# Buttons.net
KiCad netlist of a schematic drawn in Altium Designer
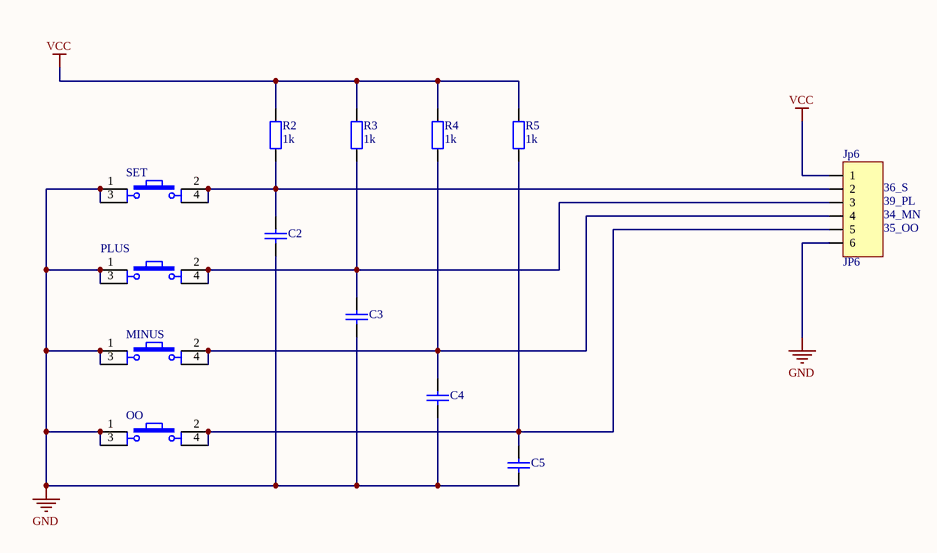
[diagram p0: Buttons.SchDoc]

(export (version "E")
  (design (tool "Eeschema 10.0.6"))
  (components
    (comp (ref "C2")
      (value "Capacitor Ceramic")
      (footprint "C0805")
      (description "Capacitor")
      (fields (field (name "PUBLISHER") "Altium Limited"))
      (libsource (lib "NBBLib 14-03-2012") (part "CapSMD"))
    )
    (comp (ref "C3")
      (value "Capacitor Ceramic")
      (footprint "C0805")
      (description "Capacitor")
      (fields (field (name "PUBLISHER") "Altium Limited"))
      (libsource (lib "NBBLib 14-03-2012") (part "CapSMD"))
    )
    (comp (ref "C4")
      (value "Capacitor Ceramic")
      (footprint "C0805")
      (description "Capacitor")
      (fields (field (name "PUBLISHER") "Altium Limited"))
      (libsource (lib "NBBLib 14-03-2012") (part "CapSMD"))
    )
    (comp (ref "C5")
      (value "Capacitor Ceramic")
      (footprint "C0805")
      (description "Capacitor")
      (fields (field (name "PUBLISHER") "Altium Limited"))
      (libsource (lib "NBBLib 14-03-2012") (part "CapSMD"))
    )
    (comp (ref "Jp6")
      (value "JP6")
      (footprint "JP6-C1T")
      (description "WR-PHD 2.54 mm Angled Socket Header")
      (fields
        (field (name "MANUFACTURER") "Würth Elektronik eiSos GmbH")
        (field (name "PARTNO") "613006143121")
        (field (name "CREATED BY") "Karrer Zheng")
      )
      (libsource (lib "LIBRARY_1") (part "JP6"))
    )
    (comp (ref "MINUS")
      (value "SW")
      (footprint "SW4")
      (description "Switch button 4 pin")
      (libsource (lib "syhaunguyen_1") (part "SW4"))
    )
    (comp (ref "OO")
      (value "SW")
      (footprint "SW4")
      (description "Switch button 4 pin")
      (libsource (lib "syhaunguyen_1") (part "SW4"))
    )
    (comp (ref "PLUS")
      (value "SW")
      (footprint "SW4")
      (description "Switch button 4 pin")
      (libsource (lib "syhaunguyen_1") (part "SW4"))
    )
    (comp (ref "R2")
      (value "1k")
      (footprint "R1/4W")
      (description "Resistor 1/4W")
      (libsource (lib "syhaunguyen_1") (part "R1/4W"))
    )
    (comp (ref "R3")
      (value "1k")
      (footprint "R1/4W")
      (description "Resistor 1/4W")
      (libsource (lib "syhaunguyen_1") (part "R1/4W"))
    )
    (comp (ref "R4")
      (value "1k")
      (footprint "R1/4W")
      (description "Resistor 1/4W")
      (libsource (lib "syhaunguyen_1") (part "R1/4W"))
    )
    (comp (ref "R5")
      (value "1k")
      (footprint "R1/4W")
      (description "Resistor 1/4W")
      (libsource (lib "syhaunguyen_1") (part "R1/4W"))
    )
    (comp (ref "SET")
      (value "SW")
      (footprint "SW4")
      (description "Switch button 4 pin")
      (libsource (lib "syhaunguyen_1") (part "SW4"))
    )
  )
  (nets
    (net (code "1") (name "GND") (class "Default")
      (node (ref "C2") (pin "1") (pinfunction "1_1") (pintype "passive"))
      (node (ref "C3") (pin "1") (pinfunction "1_1") (pintype "passive"))
      (node (ref "C4") (pin "1") (pinfunction "1_1") (pintype "passive"))
      (node (ref "C5") (pin "1") (pinfunction "1_1") (pintype "passive"))
      (node (ref "Jp6") (pin "6") (pinfunction "6_6") (pintype "passive"))
      (node (ref "MINUS") (pin "1") (pintype "passive"))
      (node (ref "MINUS") (pin "3") (pintype "passive"))
      (node (ref "OO") (pin "1") (pintype "passive"))
      (node (ref "OO") (pin "3") (pintype "passive"))
      (node (ref "PLUS") (pin "1") (pintype "passive"))
      (node (ref "PLUS") (pin "3") (pintype "passive"))
      (node (ref "SET") (pin "1") (pintype "passive"))
      (node (ref "SET") (pin "3") (pintype "passive"))
    )
    (net (code "2") (name "Net-(C2-Pad2)") (class "Default")
      (node (ref "C2") (pin "2") (pinfunction "2_2") (pintype "passive"))
      (node (ref "Jp6") (pin "2") (pinfunction "2_2") (pintype "passive"))
      (node (ref "R2") (pin "1") (pinfunction "1_1") (pintype "passive"))
      (node (ref "SET") (pin "2") (pintype "passive"))
      (node (ref "SET") (pin "4") (pintype "passive"))
    )
    (net (code "3") (name "Net-(C3-Pad2)") (class "Default")
      (node (ref "C3") (pin "2") (pinfunction "2_2") (pintype "passive"))
      (node (ref "Jp6") (pin "3") (pinfunction "3_3") (pintype "passive"))
      (node (ref "PLUS") (pin "2") (pintype "passive"))
      (node (ref "PLUS") (pin "4") (pintype "passive"))
      (node (ref "R3") (pin "1") (pinfunction "1_1") (pintype "passive"))
    )
    (net (code "4") (name "Net-(C4-Pad2)") (class "Default")
      (node (ref "C4") (pin "2") (pinfunction "2_2") (pintype "passive"))
      (node (ref "Jp6") (pin "4") (pinfunction "4_4") (pintype "passive"))
      (node (ref "MINUS") (pin "2") (pintype "passive"))
      (node (ref "MINUS") (pin "4") (pintype "passive"))
      (node (ref "R4") (pin "1") (pinfunction "1_1") (pintype "passive"))
    )
    (net (code "5") (name "Net-(C5-Pad2)") (class "Default")
      (node (ref "C5") (pin "2") (pinfunction "2_2") (pintype "passive"))
      (node (ref "Jp6") (pin "5") (pinfunction "5_5") (pintype "passive"))
      (node (ref "OO") (pin "2") (pintype "passive"))
      (node (ref "OO") (pin "4") (pintype "passive"))
      (node (ref "R5") (pin "1") (pinfunction "1_1") (pintype "passive"))
    )
    (net (code "6") (name "VCC") (class "Default")
      (node (ref "Jp6") (pin "1") (pinfunction "1_1") (pintype "passive"))
      (node (ref "R2") (pin "2") (pinfunction "2_2") (pintype "passive"))
      (node (ref "R3") (pin "2") (pinfunction "2_2") (pintype "passive"))
      (node (ref "R4") (pin "2") (pinfunction "2_2") (pintype "passive"))
      (node (ref "R5") (pin "2") (pinfunction "2_2") (pintype "passive"))
    )
  )
)
